# 1-Schematic_STM32PCB.net
KiCad netlist of a schematic drawn in EasyEDA
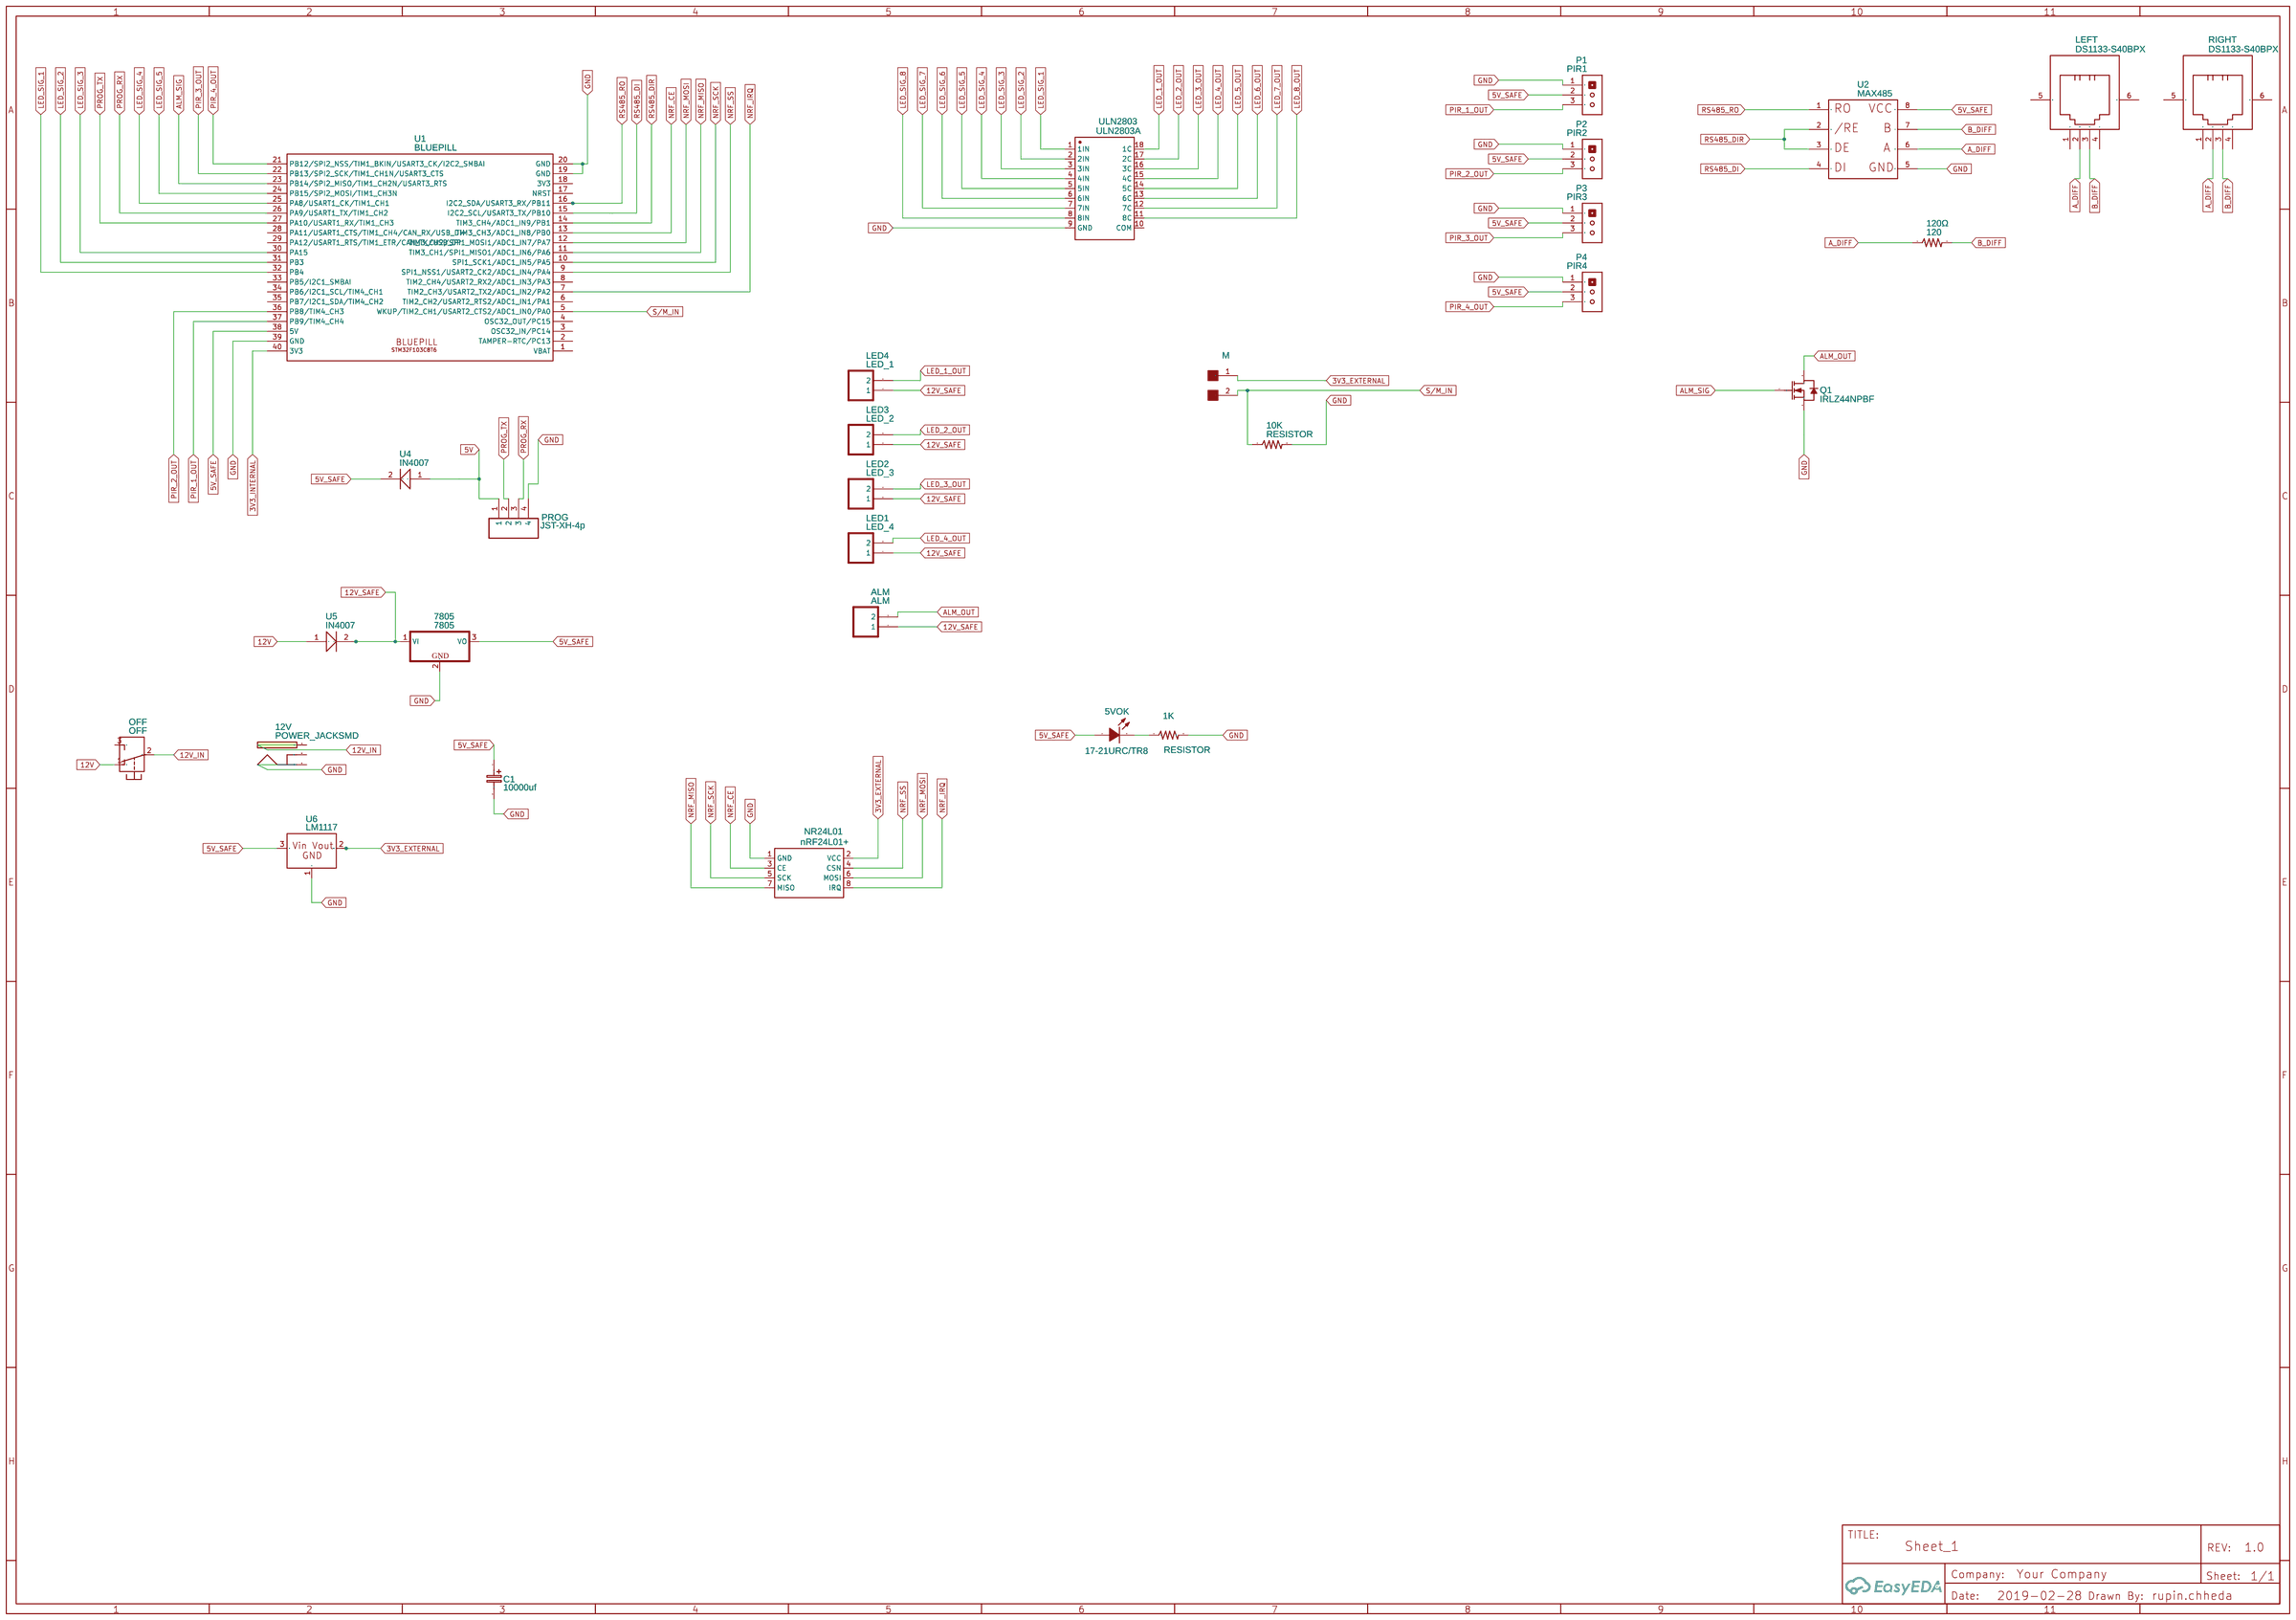
[diagram p0: schematic sheet]

(export (version "E")
  (design (tool "Eeschema 10.0.6"))
  (components
    (comp (ref "1K")
      (value "RESISTOR")
      (fields (field (name "BOM_Manufacturer Part") "?"))
      (libsource (lib "") (part "Unknown_1180_740"))
    )
    (comp (ref "5VOK")
      (value "17-21URC/TR8")
      (fields (field (name "BOM_Supplier Part") "C264414"))
      (libsource (lib "") (part "Unknown_1125_740"))
    )
    (comp (ref "10K")
      (value "RESISTOR")
      (fields (field (name "BOM_Manufacturer Part") "?"))
      (libsource (lib "") (part "Unknown_1285_445"))
    )
    (comp (ref "12V")
      (value "POWER_JACKSMD")
      (fields (field (name "BOM_Manufacturer Part") "?"))
      (libsource (lib "") (part "Unknown_280_760"))
    )
    (comp (ref "120Ω")
      (value "120")
      (fields (field (name "BOM_Manufacturer Part") "?"))
      (libsource (lib "") (part "Unknown_1955_230"))
    )
    (comp (ref "7805")
      (value "7805")
      (fields (field (name "BOM_Manufacturer Part") "?"))
      (libsource (lib "") (part "Unknown_440_645"))
    )
    (comp (ref "ALM")
      (value "ALM")
      (fields (field (name "BOM_Manufacturer Part") "?") (field (name "BOM_Supplier Part") "455-2257-ND"))
      (libsource (lib "") (part "Unknown_860_610"))
    )
    (comp (ref "C1")
      (value "10000uf")
      (fields (field (name "BOM_Manufacturer Part") "?"))
      (libsource (lib "") (part "Electrolytic_Capacitor"))
    )
    (comp (ref "LED1")
      (value "LED_4")
      (fields (field (name "BOM_Manufacturer Part") "?") (field (name "BOM_Supplier Part") "455-2257-ND"))
      (libsource (lib "") (part "Unknown_855_535"))
    )
    (comp (ref "LED2")
      (value "LED_3")
      (fields (field (name "BOM_Manufacturer Part") "?") (field (name "BOM_Supplier Part") "455-2257-ND"))
      (libsource (lib "") (part "Unknown_855_480"))
    )
    (comp (ref "LED3")
      (value "LED_2")
      (fields (field (name "BOM_Manufacturer Part") "?") (field (name "BOM_Supplier Part") "455-2257-ND"))
      (libsource (lib "") (part "Unknown_855_425"))
    )
    (comp (ref "LED4")
      (value "LED_1")
      (fields (field (name "BOM_Manufacturer Part") "?") (field (name "BOM_Supplier Part") "455-2257-ND"))
      (libsource (lib "") (part "Unknown_855_370"))
    )
    (comp (ref "LEFT")
      (value "DS1133-S40BPX")
      (fields (field (name "BOM_Supplier Part") "C77856"))
      (libsource (lib "") (part "Unknown_2110_95"))
    )
    (comp (ref "M") (value "Jumper 1x2 75mil square") (libsource (lib "") (part "Unknown_1230_375")))
    (comp (ref "NR24L01")
      (value "nRF24L01+")
      (fields (field (name "BOM_Manufacturer Part") "?"))
      (libsource (lib "") (part "Unknown_820_875"))
    )
    (comp (ref "OFF")
      (value "OFF")
      (fields (field (name "BOM_Manufacturer Part") "?"))
      (libsource (lib "") (part "Unknown_130_765"))
    )
    (comp (ref "P1")
      (value "PIR1")
      (fields (field (name "BOM_Manufacturer Part") "?") (field (name "BOM_Supplier Part") "undefined"))
      (libsource (lib "") (part "Unknown_1620_70"))
    )
    (comp (ref "P2")
      (value "PIR2")
      (fields (field (name "BOM_Manufacturer Part") "?") (field (name "BOM_Supplier Part") "undefined"))
      (libsource (lib "") (part "Unknown_1620_135"))
    )
    (comp (ref "P3")
      (value "PIR3")
      (fields (field (name "BOM_Manufacturer Part") "?") (field (name "BOM_Supplier Part") "undefined"))
      (libsource (lib "") (part "Unknown_1620_200"))
    )
    (comp (ref "P4")
      (value "PIR4")
      (fields (field (name "BOM_Manufacturer Part") "?") (field (name "BOM_Supplier Part") "undefined"))
      (libsource (lib "") (part "Unknown_1620_270"))
    )
    (comp (ref "PROG")
      (value "JST-XH-4p")
      (fields (field (name "BOM_Manufacturer Part") "?") (field (name "BOM_Supplier Part") "C5663"))
      (libsource (lib "") (part "Unknown_520_530"))
    )
    (comp (ref "Q1")
      (value "IRLZ44NPBF")
      (fields (field (name "BOM_Supplier Part") "C38774"))
      (libsource (lib "") (part "Unknown_1815_390"))
    )
    (comp (ref "RIGHT")
      (value "DS1133-S40BPX")
      (fields (field (name "BOM_Supplier Part") "C77856"))
      (libsource (lib "") (part "Unknown_2245_95"))
    )
    (comp (ref "U1")
      (value "BLUEPILL")
      (fields (field (name "BOM_Manufacturer Part") "?") (field (name "BOM_Supplier Part") "undefined"))
      (libsource (lib "") (part "Unknown_415_260"))
    )
    (comp (ref "U2")
      (value "MAX485")
      (fields (field (name "BOM_Supplier Part") "251-9431"))
      (libsource (lib "") (part "Unknown_1870_125"))
    )
    (comp (ref "U4") (value "IN4007") (libsource (lib "") (part "Unknown_400_480")))
    (comp (ref "U5") (value "IN4007") (libsource (lib "") (part "Unknown_335_645")))
    (comp (ref "U6")
      (value "LM1117")
      (fields (field (name "BOM_Manufacturer Part") "?"))
      (libsource (lib "") (part "Unknown_310_855"))
    )
    (comp (ref "ULN2803")
      (value "ULN2803A")
      (fields (field (name "BOM_Supplier Part") "C73936"))
      (libsource (lib "") (part "Unknown_1115_185"))
    )
  )
  (nets
    (net (code "1") (name "3V3_EXTERNAL") (class "Default")
      (node (ref "M") (pin "1") (pinfunction "1_1") (pintype "unspecified"))
      (node (ref "NR24L01") (pin "2") (pinfunction "VCC_2") (pintype "unspecified"))
      (node (ref "U6") (pin "2") (pinfunction "Vout_2") (pintype "unspecified"))
    )
    (net (code "2") (name "3V3_INTERNAL") (class "Default")
      (node (ref "U1") (pin "40") (pinfunction "3V3_40") (pintype "unspecified"))
    )
    (net (code "3") (name "5V") (class "Default")
      (node (ref "PROG") (pin "1") (pinfunction "1_1") (pintype "unspecified"))
      (node (ref "U4") (pin "1") (pinfunction "A_1") (pintype "unspecified"))
    )
    (net (code "4") (name "5V_SAFE") (class "Default")
      (node (ref "5VOK") (pin "1") (pinfunction "A_1") (pintype "unspecified"))
      (node (ref "7805") (pin "3") (pinfunction "VO_3") (pintype "unspecified"))
      (node (ref "C1") (pin "1") (pinfunction "1_1") (pintype "unspecified"))
      (node (ref "P1") (pin "2") (pinfunction "2_2") (pintype "unspecified"))
      (node (ref "P2") (pin "2") (pinfunction "2_2") (pintype "unspecified"))
      (node (ref "P3") (pin "2") (pinfunction "2_2") (pintype "unspecified"))
      (node (ref "P4") (pin "2") (pinfunction "2_2") (pintype "unspecified"))
      (node (ref "U1") (pin "38") (pinfunction "5V_38") (pintype "unspecified"))
      (node (ref "U2") (pin "8") (pinfunction "8_8") (pintype "unspecified"))
      (node (ref "U4") (pin "2") (pinfunction "K_2") (pintype "unspecified"))
      (node (ref "U6") (pin "3") (pinfunction "Vin_3") (pintype "passive"))
    )
    (net (code "5") (name "12V") (class "Default")
      (node (ref "OFF") (pin "1") (pinfunction "O_1") (pintype "bidirectional"))
      (node (ref "U5") (pin "1") (pinfunction "A_1") (pintype "unspecified"))
    )
    (net (code "6") (name "12V_IN") (class "Default")
      (node (ref "12V") (pin "VIN0") (pinfunction "PWR_VIN0") (pintype "unspecified"))
      (node (ref "OFF") (pin "2") (pinfunction "P_2") (pintype "bidirectional"))
    )
    (net (code "7") (name "12V_SAFE") (class "Default")
      (node (ref "7805") (pin "1") (pinfunction "VI_1") (pintype "input"))
      (node (ref "ALM") (pin "1") (pinfunction "1_1") (pintype "unspecified"))
      (node (ref "LED1") (pin "1") (pinfunction "1_1") (pintype "unspecified"))
      (node (ref "LED2") (pin "1") (pinfunction "1_1") (pintype "unspecified"))
      (node (ref "LED3") (pin "1") (pinfunction "1_1") (pintype "unspecified"))
      (node (ref "LED4") (pin "1") (pinfunction "1_1") (pintype "unspecified"))
      (node (ref "U5") (pin "2") (pinfunction "K_2") (pintype "unspecified"))
    )
    (net (code "8") (name "ALM_OUT") (class "Default")
      (node (ref "ALM") (pin "2") (pinfunction "2_2") (pintype "unspecified"))
      (node (ref "Q1") (pin "2") (pinfunction "D_2") (pintype "unspecified"))
    )
    (net (code "9") (name "ALM_SIG") (class "Default")
      (node (ref "Q1") (pin "1") (pinfunction "G_1") (pintype "unspecified"))
      (node (ref "U1") (pin "23") (pinfunction "PB14/SPI2_MISO/TIM1_CH2N/USART3_RTS_23") (pintype "unspecified"))
    )
    (net (code "10") (name "A_DIFF") (class "Default")
      (node (ref "120Ω") (pin "1") (pinfunction "1_1") (pintype "unspecified"))
      (node (ref "LEFT") (pin "2") (pinfunction "2_2") (pintype "unspecified"))
      (node (ref "RIGHT") (pin "2") (pinfunction "2_2") (pintype "unspecified"))
      (node (ref "U2") (pin "6") (pinfunction "6_6") (pintype "unspecified"))
    )
    (net (code "11") (name "B_DIFF") (class "Default")
      (node (ref "120Ω") (pin "2") (pinfunction "2_2") (pintype "unspecified"))
      (node (ref "LEFT") (pin "3") (pinfunction "3_3") (pintype "unspecified"))
      (node (ref "RIGHT") (pin "3") (pinfunction "3_3") (pintype "unspecified"))
      (node (ref "U2") (pin "7") (pinfunction "7_7") (pintype "unspecified"))
    )
    (net (code "12") (name "GND") (class "Default")
      (node (ref "10K") (pin "2") (pinfunction "2_2") (pintype "unspecified"))
      (node (ref "12V") (pin "P$4") (pinfunction "GND_P$4") (pintype "unspecified"))
      (node (ref "1K") (pin "2") (pinfunction "2_2") (pintype "unspecified"))
      (node (ref "7805") (pin "2") (pinfunction "GND_2") (pintype "unspecified"))
      (node (ref "C1") (pin "2") (pinfunction "2_2") (pintype "unspecified"))
      (node (ref "NR24L01") (pin "1") (pinfunction "GND_1") (pintype "unspecified"))
      (node (ref "P1") (pin "1") (pinfunction "1_1") (pintype "unspecified"))
      (node (ref "P2") (pin "1") (pinfunction "1_1") (pintype "unspecified"))
      (node (ref "P3") (pin "1") (pinfunction "1_1") (pintype "unspecified"))
      (node (ref "P4") (pin "1") (pinfunction "1_1") (pintype "unspecified"))
      (node (ref "PROG") (pin "4") (pinfunction "4_4") (pintype "unspecified"))
      (node (ref "Q1") (pin "3") (pinfunction "S_3") (pintype "unspecified"))
      (node (ref "U1") (pin "19") (pinfunction "GND_19") (pintype "unspecified"))
      (node (ref "U1") (pin "20") (pinfunction "GND_20") (pintype "unspecified"))
      (node (ref "U1") (pin "39") (pinfunction "GND_39") (pintype "unspecified"))
      (node (ref "U2") (pin "5") (pinfunction "5_5") (pintype "unspecified"))
      (node (ref "U6") (pin "1") (pinfunction "Vin_1") (pintype "passive"))
      (node (ref "ULN2803") (pin "9") (pinfunction "GND_9") (pintype "unspecified"))
    )
    (net (code "13") (name "LED_1_OUT") (class "Default")
      (node (ref "LED4") (pin "2") (pinfunction "2_2") (pintype "unspecified"))
      (node (ref "ULN2803") (pin "18") (pinfunction "1C_18") (pintype "unspecified"))
    )
    (net (code "14") (name "LED_2_OUT") (class "Default")
      (node (ref "LED3") (pin "2") (pinfunction "2_2") (pintype "unspecified"))
      (node (ref "ULN2803") (pin "17") (pinfunction "2C_17") (pintype "unspecified"))
    )
    (net (code "15") (name "LED_3_OUT") (class "Default")
      (node (ref "LED2") (pin "2") (pinfunction "2_2") (pintype "unspecified"))
      (node (ref "ULN2803") (pin "16") (pinfunction "3C_16") (pintype "unspecified"))
    )
    (net (code "16") (name "LED_4_OUT") (class "Default")
      (node (ref "LED1") (pin "2") (pinfunction "2_2") (pintype "unspecified"))
      (node (ref "ULN2803") (pin "15") (pinfunction "4C_15") (pintype "unspecified"))
    )
    (net (code "17") (name "LED_5_OUT") (class "Default")
      (node (ref "ULN2803") (pin "14") (pinfunction "5C_14") (pintype "unspecified"))
    )
    (net (code "18") (name "LED_6_OUT") (class "Default")
      (node (ref "ULN2803") (pin "13") (pinfunction "6C_13") (pintype "unspecified"))
    )
    (net (code "19") (name "LED_7_OUT") (class "Default")
      (node (ref "ULN2803") (pin "12") (pinfunction "7C_12") (pintype "unspecified"))
    )
    (net (code "20") (name "LED_8_OUT") (class "Default")
      (node (ref "ULN2803") (pin "11") (pinfunction "8C_11") (pintype "unspecified"))
    )
    (net (code "21") (name "LED_SIG_1") (class "Default")
      (node (ref "U1") (pin "32") (pinfunction "PB4_32") (pintype "unspecified"))
      (node (ref "ULN2803") (pin "1") (pinfunction "1IN_1") (pintype "unspecified"))
    )
    (net (code "22") (name "LED_SIG_2") (class "Default")
      (node (ref "U1") (pin "31") (pinfunction "PB3_31") (pintype "unspecified"))
      (node (ref "ULN2803") (pin "2") (pinfunction "2IN_2") (pintype "unspecified"))
    )
    (net (code "23") (name "LED_SIG_3") (class "Default")
      (node (ref "U1") (pin "30") (pinfunction "PA15_30") (pintype "unspecified"))
      (node (ref "ULN2803") (pin "3") (pinfunction "3IN_3") (pintype "unspecified"))
    )
    (net (code "24") (name "LED_SIG_4") (class "Default")
      (node (ref "U1") (pin "25") (pinfunction "PA8/USART1_CK/TIM1_CH1_25") (pintype "unspecified"))
      (node (ref "ULN2803") (pin "4") (pinfunction "4IN_4") (pintype "unspecified"))
    )
    (net (code "25") (name "LED_SIG_5") (class "Default")
      (node (ref "U1") (pin "24") (pinfunction "PB15/SPI2_MOSI/TIM1_CH3N_24") (pintype "unspecified"))
      (node (ref "ULN2803") (pin "5") (pinfunction "5IN_5") (pintype "unspecified"))
    )
    (net (code "26") (name "LED_SIG_6") (class "Default")
      (node (ref "ULN2803") (pin "6") (pinfunction "6IN_6") (pintype "unspecified"))
    )
    (net (code "27") (name "LED_SIG_7") (class "Default")
      (node (ref "ULN2803") (pin "7") (pinfunction "7IN_7") (pintype "unspecified"))
    )
    (net (code "28") (name "LED_SIG_8") (class "Default")
      (node (ref "ULN2803") (pin "8") (pinfunction "8IN_8") (pintype "unspecified"))
    )
    (net (code "29") (name "NRF_CE") (class "Default")
      (node (ref "NR24L01") (pin "3") (pinfunction "CE_3") (pintype "unspecified"))
      (node (ref "U1") (pin "13") (pinfunction "TIM3_CH3/ADC1_IN8/PB0_13") (pintype "unspecified"))
    )
    (net (code "30") (name "NRF_IRQ") (class "Default")
      (node (ref "NR24L01") (pin "8") (pinfunction "IRQ_8") (pintype "unspecified"))
      (node (ref "U1") (pin "7") (pinfunction "TIM2_CH3/USART2_TX2/ADC1_IN2/PA2_7") (pintype "unspecified"))
    )
    (net (code "31") (name "NRF_MISO") (class "Default")
      (node (ref "NR24L01") (pin "7") (pinfunction "MISO_7") (pintype "unspecified"))
      (node (ref "U1") (pin "11") (pinfunction "TIM3_CH1/SPI1_MISO1/ADC1_IN6/PA6_11") (pintype "unspecified"))
    )
    (net (code "32") (name "NRF_MOSI") (class "Default")
      (node (ref "NR24L01") (pin "6") (pinfunction "MOSI_6") (pintype "unspecified"))
      (node (ref "U1") (pin "12") (pinfunction "TIM3_CH2/SPI1_MOSI1/ADC1_IN7/PA7_12") (pintype "unspecified"))
    )
    (net (code "33") (name "NRF_SCK") (class "Default")
      (node (ref "NR24L01") (pin "5") (pinfunction "SCK_5") (pintype "unspecified"))
      (node (ref "U1") (pin "10") (pinfunction "SPI1_SCK1/ADC1_IN5/PA5_10") (pintype "unspecified"))
    )
    (net (code "34") (name "NRF_SS") (class "Default")
      (node (ref "NR24L01") (pin "4") (pinfunction "CSN_4") (pintype "unspecified"))
      (node (ref "U1") (pin "9") (pinfunction "SPI1_NSS1/USART2_CK2/ADC1_IN4/PA4_9") (pintype "unspecified"))
    )
    (net (code "35") (name "Net-(5VOK-K)") (class "Default")
      (node (ref "1K") (pin "1") (pinfunction "1_1") (pintype "unspecified"))
      (node (ref "5VOK") (pin "2") (pinfunction "K_2") (pintype "unspecified"))
    )
    (net (code "36") (name "PIR_1_OUT") (class "Default")
      (node (ref "P1") (pin "3") (pinfunction "3_3") (pintype "unspecified"))
      (node (ref "U1") (pin "37") (pinfunction "PB9/TIM4_CH4_37") (pintype "unspecified"))
    )
    (net (code "37") (name "PIR_2_OUT") (class "Default")
      (node (ref "P2") (pin "3") (pinfunction "3_3") (pintype "unspecified"))
      (node (ref "U1") (pin "36") (pinfunction "PB8/TIM4_CH3_36") (pintype "unspecified"))
    )
    (net (code "38") (name "PIR_3_OUT") (class "Default")
      (node (ref "P3") (pin "3") (pinfunction "3_3") (pintype "unspecified"))
      (node (ref "U1") (pin "22") (pinfunction "PB13/SPI2_SCK/TIM1_CH1N/USART3_CTS_22") (pintype "unspecified"))
    )
    (net (code "39") (name "PIR_4_OUT") (class "Default")
      (node (ref "P4") (pin "3") (pinfunction "3_3") (pintype "unspecified"))
      (node (ref "U1") (pin "21") (pinfunction "PB12/SPI2_NSS/TIM1_BKIN/USART3_CK/I2C2_SMBAI_21") (pintype "unspecified"))
    )
    (net (code "40") (name "PROG_RX") (class "Default")
      (node (ref "PROG") (pin "3") (pinfunction "3_3") (pintype "unspecified"))
      (node (ref "U1") (pin "26") (pinfunction "PA9/USART1_TX/TIM1_CH2_26") (pintype "unspecified"))
    )
    (net (code "41") (name "PROG_TX") (class "Default")
      (node (ref "PROG") (pin "2") (pinfunction "2_2") (pintype "unspecified"))
      (node (ref "U1") (pin "27") (pinfunction "PA10/USART1_RX/TIM1_CH3_27") (pintype "unspecified"))
    )
    (net (code "42") (name "RS485_DI") (class "Default")
      (node (ref "U1") (pin "15") (pinfunction "I2C2_SCL/USART3_TX/PB10_15") (pintype "unspecified"))
      (node (ref "U2") (pin "4") (pinfunction "4_4") (pintype "unspecified"))
    )
    (net (code "43") (name "RS485_DIR") (class "Default")
      (node (ref "U1") (pin "14") (pinfunction "TIM3_CH4/ADC1_IN9/PB1_14") (pintype "unspecified"))
      (node (ref "U2") (pin "2") (pinfunction "2_2") (pintype "unspecified"))
      (node (ref "U2") (pin "3") (pinfunction "3_3") (pintype "unspecified"))
    )
    (net (code "44") (name "RS485_RO") (class "Default")
      (node (ref "U1") (pin "16") (pinfunction "I2C2_SDA/USART3_RX/PB11_16") (pintype "unspecified"))
      (node (ref "U2") (pin "1") (pinfunction "1_1") (pintype "unspecified"))
    )
    (net (code "45") (name "S{slash}M_IN") (class "Default")
      (node (ref "10K") (pin "1") (pinfunction "1_1") (pintype "unspecified"))
      (node (ref "M") (pin "2") (pinfunction "2_2") (pintype "unspecified"))
      (node (ref "U1") (pin "5") (pinfunction "WKUP/TIM2_CH1/USART2_CTS2/ADC1_IN0/PA0_5") (pintype "unspecified"))
    )
    (net (code "46") (name "unconnected-(12V-GNDBREAK-PadGND)") (class "Default")
      (node (ref "12V") (pin "GND") (pinfunction "GNDBREAK_GND") (pintype "unspecified"))
    )
    (net (code "47") (name "unconnected-(LEFT-Pad1)") (class "Default")
      (node (ref "LEFT") (pin "1") (pinfunction "1_1") (pintype "unspecified"))
    )
    (net (code "48") (name "unconnected-(LEFT-Pad4)") (class "Default")
      (node (ref "LEFT") (pin "4") (pinfunction "4_4") (pintype "unspecified"))
    )
    (net (code "49") (name "unconnected-(LEFT-Pad5)") (class "Default")
      (node (ref "LEFT") (pin "5") (pinfunction "5_5") (pintype "unspecified"))
    )
    (net (code "50") (name "unconnected-(LEFT-Pad6)") (class "Default")
      (node (ref "LEFT") (pin "6") (pinfunction "6_6") (pintype "unspecified"))
    )
    (net (code "51") (name "unconnected-(OFF-S-Pad3)") (class "Default")
      (node (ref "OFF") (pin "3") (pinfunction "S_3") (pintype "bidirectional"))
    )
    (net (code "52") (name "unconnected-(RIGHT-Pad1)") (class "Default")
      (node (ref "RIGHT") (pin "1") (pinfunction "1_1") (pintype "unspecified"))
    )
    (net (code "53") (name "unconnected-(RIGHT-Pad4)") (class "Default")
      (node (ref "RIGHT") (pin "4") (pinfunction "4_4") (pintype "unspecified"))
    )
    (net (code "54") (name "unconnected-(RIGHT-Pad5)") (class "Default")
      (node (ref "RIGHT") (pin "5") (pinfunction "5_5") (pintype "unspecified"))
    )
    (net (code "55") (name "unconnected-(RIGHT-Pad6)") (class "Default")
      (node (ref "RIGHT") (pin "6") (pinfunction "6_6") (pintype "unspecified"))
    )
    (net (code "56") (name "unconnected-(U1-3V3-Pad18)") (class "Default")
      (node (ref "U1") (pin "18") (pinfunction "3V3_18") (pintype "unspecified"))
    )
    (net (code "57") (name "unconnected-(U1-NRST-Pad17)") (class "Default")
      (node (ref "U1") (pin "17") (pinfunction "NRST_17") (pintype "unspecified"))
    )
    (net (code "58") (name "unconnected-(U1-OSC32_IN{slash}PC14-Pad3)") (class "Default")
      (node (ref "U1") (pin "3") (pinfunction "OSC32_IN/PC14_3") (pintype "unspecified"))
    )
    (net (code "59") (name "unconnected-(U1-OSC32_OUT{slash}PC15-Pad4)") (class "Default")
      (node (ref "U1") (pin "4") (pinfunction "OSC32_OUT/PC15_4") (pintype "unspecified"))
    )
    (net (code "60") (name "unconnected-(U1-PA11{slash}USART1_CTS{slash}TIM1_CH4{slash}CAN_RX{slash}USB_DM-Pad28)") (class "Default")
      (node (ref "U1") (pin "28") (pinfunction "PA11/USART1_CTS/TIM1_CH4/CAN_RX/USB_DM_28") (pintype "unspecified"))
    )
    (net (code "61") (name "unconnected-(U1-PA12{slash}USART1_RTS{slash}TIM1_ETR{slash}CAN_TX{slash}USB_DP-Pad29)") (class "Default")
      (node (ref "U1") (pin "29") (pinfunction "PA12/USART1_RTS/TIM1_ETR/CAN_TX/USB_DP_29") (pintype "unspecified"))
    )
    (net (code "62") (name "unconnected-(U1-PB5{slash}I2C1_SMBAI-Pad33)") (class "Default")
      (node (ref "U1") (pin "33") (pinfunction "PB5/I2C1_SMBAI_33") (pintype "unspecified"))
    )
    (net (code "63") (name "unconnected-(U1-PB6{slash}I2C1_SCL{slash}TIM4_CH1-Pad34)") (class "Default")
      (node (ref "U1") (pin "34") (pinfunction "PB6/I2C1_SCL/TIM4_CH1_34") (pintype "unspecified"))
    )
    (net (code "64") (name "unconnected-(U1-PB7{slash}I2C1_SDA{slash}TIM4_CH2-Pad35)") (class "Default")
      (node (ref "U1") (pin "35") (pinfunction "PB7/I2C1_SDA/TIM4_CH2_35") (pintype "unspecified"))
    )
    (net (code "65") (name "unconnected-(U1-TAMPER-RTC{slash}PC13-Pad2)") (class "Default")
      (node (ref "U1") (pin "2") (pinfunction "TAMPER-RTC/PC13_2") (pintype "unspecified"))
    )
    (net (code "66") (name "unconnected-(U1-TIM2_CH2{slash}USART2_RTS2{slash}ADC1_IN1{slash}PA1-Pad6)") (class "Default")
      (node (ref "U1") (pin "6") (pinfunction "TIM2_CH2/USART2_RTS2/ADC1_IN1/PA1_6") (pintype "unspecified"))
    )
    (net (code "67") (name "unconnected-(U1-TIM2_CH4{slash}USART2_RX2{slash}ADC1_IN3{slash}PA3-Pad8)") (class "Default")
      (node (ref "U1") (pin "8") (pinfunction "TIM2_CH4/USART2_RX2/ADC1_IN3/PA3_8") (pintype "unspecified"))
    )
    (net (code "68") (name "unconnected-(U1-VBAT-Pad1)") (class "Default")
      (node (ref "U1") (pin "1") (pinfunction "VBAT_1") (pintype "unspecified"))
    )
    (net (code "69") (name "unconnected-(ULN2803-COM-Pad10)") (class "Default")
      (node (ref "ULN2803") (pin "10") (pinfunction "COM_10") (pintype "unspecified"))
    )
  )
)
